# madrack.net
KiCad netlist of a schematic drawn in EAGLE
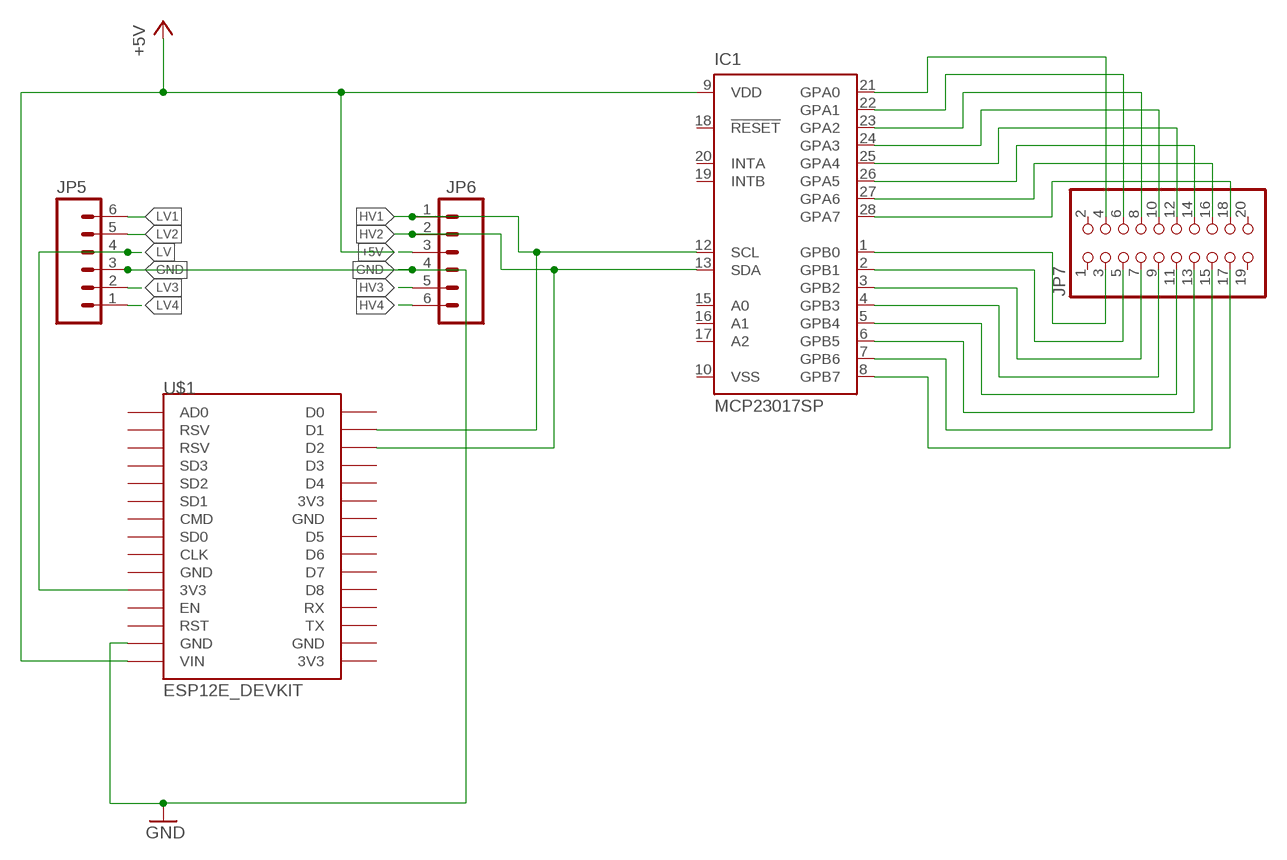
[diagram p0: schematic, sheet 1]

(export (version "E")
  (design (tool "Eeschema 10.0.6"))
  (components
    (comp (ref "IC1")
      (value "MCP23017SP")
      (footprint "eagle-import:DIL28-3")
      (libsource (lib "eagle-import") (part "MCP23017SP"))
    )
    (comp (ref "JP5")
      (value "M06SIP")
      (footprint "eagle-import:1X06")
      (libsource (lib "eagle-import") (part "M06SIP"))
    )
    (comp (ref "JP6")
      (value "M06SIP")
      (footprint "eagle-import:1X06")
      (libsource (lib "eagle-import") (part "M06SIP"))
    )
    (comp (ref "JP7")
      (value "PINHD-2X10")
      (footprint "eagle-import:2X10")
      (libsource (lib "eagle-import") (part "PINHD-2X10"))
    )
    (comp (ref "U$1")
      (value "ESP12E_DEVKIT")
      (footprint "eagle-import:ESP12E_DEVKIT")
      (libsource (lib "eagle-import") (part "ESP12E_DEVKIT"))
    )
  )
  (nets
    (net (code "1") (name "+5V") (class "Default")
      (node (ref "IC1") (pin "9") (pinfunction "VDD_9") (pintype "power_in"))
      (node (ref "JP6") (pin "3") (pinfunction "3_3") (pintype "passive"))
      (node (ref "U$1") (pin "VIN") (pinfunction "VIN_VIN") (pintype "bidirectional"))
    )
    (net (code "2") (name "/VSS") (class "Default")
      (node (ref "IC1") (pin "10") (pinfunction "VSS_10") (pintype "power_in"))
    )
    (net (code "3") (name "GND") (class "Default")
      (node (ref "JP5") (pin "3") (pinfunction "3_3") (pintype "passive"))
      (node (ref "JP6") (pin "4") (pinfunction "4_4") (pintype "passive"))
      (node (ref "U$1") (pin "GND@1") (pinfunction "GND_GND@1") (pintype "bidirectional"))
    )
    (net (code "4") (name "HV1") (class "Default")
      (node (ref "IC1") (pin "12") (pinfunction "SCL_12") (pintype "input"))
      (node (ref "JP6") (pin "1") (pinfunction "1_1") (pintype "passive"))
      (node (ref "U$1") (pin "D1") (pinfunction "D1_D1") (pintype "bidirectional"))
    )
    (net (code "5") (name "HV2") (class "Default")
      (node (ref "IC1") (pin "13") (pinfunction "SDA_13") (pintype "bidirectional"))
      (node (ref "JP6") (pin "2") (pinfunction "2_2") (pintype "passive"))
      (node (ref "U$1") (pin "D2") (pinfunction "D2_D2") (pintype "bidirectional"))
    )
    (net (code "6") (name "HV3") (class "Default")
      (node (ref "JP6") (pin "5") (pinfunction "5_5") (pintype "passive"))
    )
    (net (code "7") (name "HV4") (class "Default")
      (node (ref "JP6") (pin "6") (pinfunction "6_6") (pintype "passive"))
    )
    (net (code "8") (name "LV") (class "Default")
      (node (ref "JP5") (pin "4") (pinfunction "4_4") (pintype "passive"))
      (node (ref "U$1") (pin "3V3@0") (pinfunction "3V3_3V3@0") (pintype "bidirectional"))
    )
    (net (code "9") (name "LV1") (class "Default")
      (node (ref "JP5") (pin "6") (pinfunction "6_6") (pintype "passive"))
    )
    (net (code "10") (name "LV2") (class "Default")
      (node (ref "JP5") (pin "5") (pinfunction "5_5") (pintype "passive"))
    )
    (net (code "11") (name "LV3") (class "Default")
      (node (ref "JP5") (pin "2") (pinfunction "2_2") (pintype "passive"))
    )
    (net (code "12") (name "LV4") (class "Default")
      (node (ref "JP5") (pin "1") (pinfunction "1_1") (pintype "passive"))
    )
    (net (code "13") (name "Net-(IC1-GPA0)") (class "Default")
      (node (ref "IC1") (pin "21") (pinfunction "GPA0_21") (pintype "bidirectional"))
      (node (ref "JP7") (pin "4") (pinfunction "4_4") (pintype "passive"))
    )
    (net (code "14") (name "Net-(IC1-GPA1)") (class "Default")
      (node (ref "IC1") (pin "22") (pinfunction "GPA1_22") (pintype "bidirectional"))
      (node (ref "JP7") (pin "6") (pinfunction "6_6") (pintype "passive"))
    )
    (net (code "15") (name "Net-(IC1-GPA2)") (class "Default")
      (node (ref "IC1") (pin "23") (pinfunction "GPA2_23") (pintype "bidirectional"))
      (node (ref "JP7") (pin "8") (pinfunction "8_8") (pintype "passive"))
    )
    (net (code "16") (name "Net-(IC1-GPA3)") (class "Default")
      (node (ref "IC1") (pin "24") (pinfunction "GPA3_24") (pintype "bidirectional"))
      (node (ref "JP7") (pin "10") (pinfunction "10_10") (pintype "passive"))
    )
    (net (code "17") (name "Net-(IC1-GPA4)") (class "Default")
      (node (ref "IC1") (pin "25") (pinfunction "GPA4_25") (pintype "bidirectional"))
      (node (ref "JP7") (pin "12") (pinfunction "12_12") (pintype "passive"))
    )
    (net (code "18") (name "Net-(IC1-GPA5)") (class "Default")
      (node (ref "IC1") (pin "26") (pinfunction "GPA5_26") (pintype "bidirectional"))
      (node (ref "JP7") (pin "14") (pinfunction "14_14") (pintype "passive"))
    )
    (net (code "19") (name "Net-(IC1-GPA6)") (class "Default")
      (node (ref "IC1") (pin "27") (pinfunction "GPA6_27") (pintype "bidirectional"))
      (node (ref "JP7") (pin "16") (pinfunction "16_16") (pintype "passive"))
    )
    (net (code "20") (name "Net-(IC1-GPA7)") (class "Default")
      (node (ref "IC1") (pin "28") (pinfunction "GPA7_28") (pintype "bidirectional"))
      (node (ref "JP7") (pin "18") (pinfunction "18_18") (pintype "passive"))
    )
    (net (code "21") (name "Net-(IC1-GPB0)") (class "Default")
      (node (ref "IC1") (pin "1") (pinfunction "GPB0_1") (pintype "bidirectional"))
      (node (ref "JP7") (pin "3") (pinfunction "3_3") (pintype "passive"))
    )
    (net (code "22") (name "Net-(IC1-GPB1)") (class "Default")
      (node (ref "IC1") (pin "2") (pinfunction "GPB1_2") (pintype "bidirectional"))
      (node (ref "JP7") (pin "5") (pinfunction "5_5") (pintype "passive"))
    )
    (net (code "23") (name "Net-(IC1-GPB2)") (class "Default")
      (node (ref "IC1") (pin "3") (pinfunction "GPB2_3") (pintype "bidirectional"))
      (node (ref "JP7") (pin "7") (pinfunction "7_7") (pintype "passive"))
    )
    (net (code "24") (name "Net-(IC1-GPB3)") (class "Default")
      (node (ref "IC1") (pin "4") (pinfunction "GPB3_4") (pintype "bidirectional"))
      (node (ref "JP7") (pin "9") (pinfunction "9_9") (pintype "passive"))
    )
    (net (code "25") (name "Net-(IC1-GPB4)") (class "Default")
      (node (ref "IC1") (pin "5") (pinfunction "GPB4_5") (pintype "bidirectional"))
      (node (ref "JP7") (pin "11") (pinfunction "11_11") (pintype "passive"))
    )
    (net (code "26") (name "Net-(IC1-GPB5)") (class "Default")
      (node (ref "IC1") (pin "6") (pinfunction "GPB5_6") (pintype "bidirectional"))
      (node (ref "JP7") (pin "13") (pinfunction "13_13") (pintype "passive"))
    )
    (net (code "27") (name "Net-(IC1-GPB6)") (class "Default")
      (node (ref "IC1") (pin "7") (pinfunction "GPB6_7") (pintype "bidirectional"))
      (node (ref "JP7") (pin "15") (pinfunction "15_15") (pintype "passive"))
    )
    (net (code "28") (name "Net-(IC1-GPB7)") (class "Default")
      (node (ref "IC1") (pin "8") (pinfunction "GPB7_8") (pintype "bidirectional"))
      (node (ref "JP7") (pin "17") (pinfunction "17_17") (pintype "passive"))
    )
    (net (code "29") (name "unconnected-(IC1-A0-Pad15)") (class "Default")
      (node (ref "IC1") (pin "15") (pinfunction "A0_15") (pintype "input"))
    )
    (net (code "30") (name "unconnected-(IC1-A1-Pad16)") (class "Default")
      (node (ref "IC1") (pin "16") (pinfunction "A1_16") (pintype "input"))
    )
    (net (code "31") (name "unconnected-(IC1-A2-Pad17)") (class "Default")
      (node (ref "IC1") (pin "17") (pinfunction "A2_17") (pintype "input"))
    )
    (net (code "32") (name "unconnected-(IC1-INTA-Pad20)") (class "Default")
      (node (ref "IC1") (pin "20") (pinfunction "INTA_20") (pintype "output"))
    )
    (net (code "33") (name "unconnected-(IC1-INTB-Pad19)") (class "Default")
      (node (ref "IC1") (pin "19") (pinfunction "INTB_19") (pintype "output"))
    )
    (net (code "34") (name "unconnected-(IC1-~{RESET}-Pad18)") (class "Default")
      (node (ref "IC1") (pin "18") (pinfunction "~{RESET}_18") (pintype "input"))
    )
    (net (code "35") (name "unconnected-(JP7-Pad1)") (class "Default")
      (node (ref "JP7") (pin "1") (pinfunction "1_1") (pintype "passive"))
    )
    (net (code "36") (name "unconnected-(JP7-Pad2)") (class "Default")
      (node (ref "JP7") (pin "2") (pinfunction "2_2") (pintype "passive"))
    )
    (net (code "37") (name "unconnected-(JP7-Pad19)") (class "Default")
      (node (ref "JP7") (pin "19") (pinfunction "19_19") (pintype "passive"))
    )
    (net (code "38") (name "unconnected-(JP7-Pad20)") (class "Default")
      (node (ref "JP7") (pin "20") (pinfunction "20_20") (pintype "passive"))
    )
    (net (code "39") (name "unconnected-(U$1-3V3-Pad3V3@1)") (class "Default")
      (node (ref "U$1") (pin "3V3@1") (pinfunction "3V3_3V3@1") (pintype "bidirectional"))
    )
    (net (code "40") (name "unconnected-(U$1-3V3-Pad3V3@2)") (class "Default")
      (node (ref "U$1") (pin "3V3@2") (pinfunction "3V3_3V3@2") (pintype "bidirectional"))
    )
    (net (code "41") (name "unconnected-(U$1-GND-PadGND@0)") (class "Default")
      (node (ref "U$1") (pin "GND@0") (pinfunction "GND_GND@0") (pintype "bidirectional"))
    )
    (net (code "42") (name "unconnected-(U$1-GND-PadGND@2)") (class "Default")
      (node (ref "U$1") (pin "GND@2") (pinfunction "GND_GND@2") (pintype "bidirectional"))
    )
    (net (code "43") (name "unconnected-(U$1-GND-PadGND@3)") (class "Default")
      (node (ref "U$1") (pin "GND@3") (pinfunction "GND_GND@3") (pintype "bidirectional"))
    )
    (net (code "44") (name "unconnected-(U$1-PadAD0)") (class "Default")
      (node (ref "U$1") (pin "AD0") (pinfunction "AD0_AD0") (pintype "bidirectional"))
    )
    (net (code "45") (name "unconnected-(U$1-PadCLK)") (class "Default")
      (node (ref "U$1") (pin "CLK") (pinfunction "CLK_CLK") (pintype "bidirectional"))
    )
    (net (code "46") (name "unconnected-(U$1-PadCMD)") (class "Default")
      (node (ref "U$1") (pin "CMD") (pinfunction "CMD_CMD") (pintype "bidirectional"))
    )
    (net (code "47") (name "unconnected-(U$1-PadD0)") (class "Default")
      (node (ref "U$1") (pin "D0") (pinfunction "D0_D0") (pintype "bidirectional"))
    )
    (net (code "48") (name "unconnected-(U$1-PadD3)") (class "Default")
      (node (ref "U$1") (pin "D3") (pinfunction "D3_D3") (pintype "bidirectional"))
    )
    (net (code "49") (name "unconnected-(U$1-PadD4)") (class "Default")
      (node (ref "U$1") (pin "D4") (pinfunction "D4_D4") (pintype "bidirectional"))
    )
    (net (code "50") (name "unconnected-(U$1-PadD5)") (class "Default")
      (node (ref "U$1") (pin "D5") (pinfunction "D5_D5") (pintype "bidirectional"))
    )
    (net (code "51") (name "unconnected-(U$1-PadD6)") (class "Default")
      (node (ref "U$1") (pin "D6") (pinfunction "D6_D6") (pintype "bidirectional"))
    )
    (net (code "52") (name "unconnected-(U$1-PadD7)") (class "Default")
      (node (ref "U$1") (pin "D7") (pinfunction "D7_D7") (pintype "bidirectional"))
    )
    (net (code "53") (name "unconnected-(U$1-PadD8)") (class "Default")
      (node (ref "U$1") (pin "D8") (pinfunction "D8_D8") (pintype "bidirectional"))
    )
    (net (code "54") (name "unconnected-(U$1-PadEN)") (class "Default")
      (node (ref "U$1") (pin "EN") (pinfunction "EN_EN") (pintype "bidirectional"))
    )
    (net (code "55") (name "unconnected-(U$1-PadRST)") (class "Default")
      (node (ref "U$1") (pin "RST") (pinfunction "RST_RST") (pintype "bidirectional"))
    )
    (net (code "56") (name "unconnected-(U$1-PadRX)") (class "Default")
      (node (ref "U$1") (pin "RX") (pinfunction "RX_RX") (pintype "bidirectional"))
    )
    (net (code "57") (name "unconnected-(U$1-PadSD0)") (class "Default")
      (node (ref "U$1") (pin "SD0") (pinfunction "SD0_SD0") (pintype "bidirectional"))
    )
    (net (code "58") (name "unconnected-(U$1-PadSD1)") (class "Default")
      (node (ref "U$1") (pin "SD1") (pinfunction "SD1_SD1") (pintype "bidirectional"))
    )
    (net (code "59") (name "unconnected-(U$1-PadSD2)") (class "Default")
      (node (ref "U$1") (pin "SD2") (pinfunction "SD2_SD2") (pintype "bidirectional"))
    )
    (net (code "60") (name "unconnected-(U$1-PadSD3)") (class "Default")
      (node (ref "U$1") (pin "SD3") (pinfunction "SD3_SD3") (pintype "bidirectional"))
    )
    (net (code "61") (name "unconnected-(U$1-PadTX)") (class "Default")
      (node (ref "U$1") (pin "TX") (pinfunction "TX_TX") (pintype "bidirectional"))
    )
    (net (code "62") (name "unconnected-(U$1-RSV-PadRSV@0)") (class "Default")
      (node (ref "U$1") (pin "RSV@0") (pinfunction "RSV_RSV@0") (pintype "bidirectional"))
    )
    (net (code "63") (name "unconnected-(U$1-RSV-PadRSV@1)") (class "Default")
      (node (ref "U$1") (pin "RSV@1") (pinfunction "RSV_RSV@1") (pintype "bidirectional"))
    )
  )
)
